# ATMEGA328P.net
KiCad netlist of a schematic drawn in EAGLE
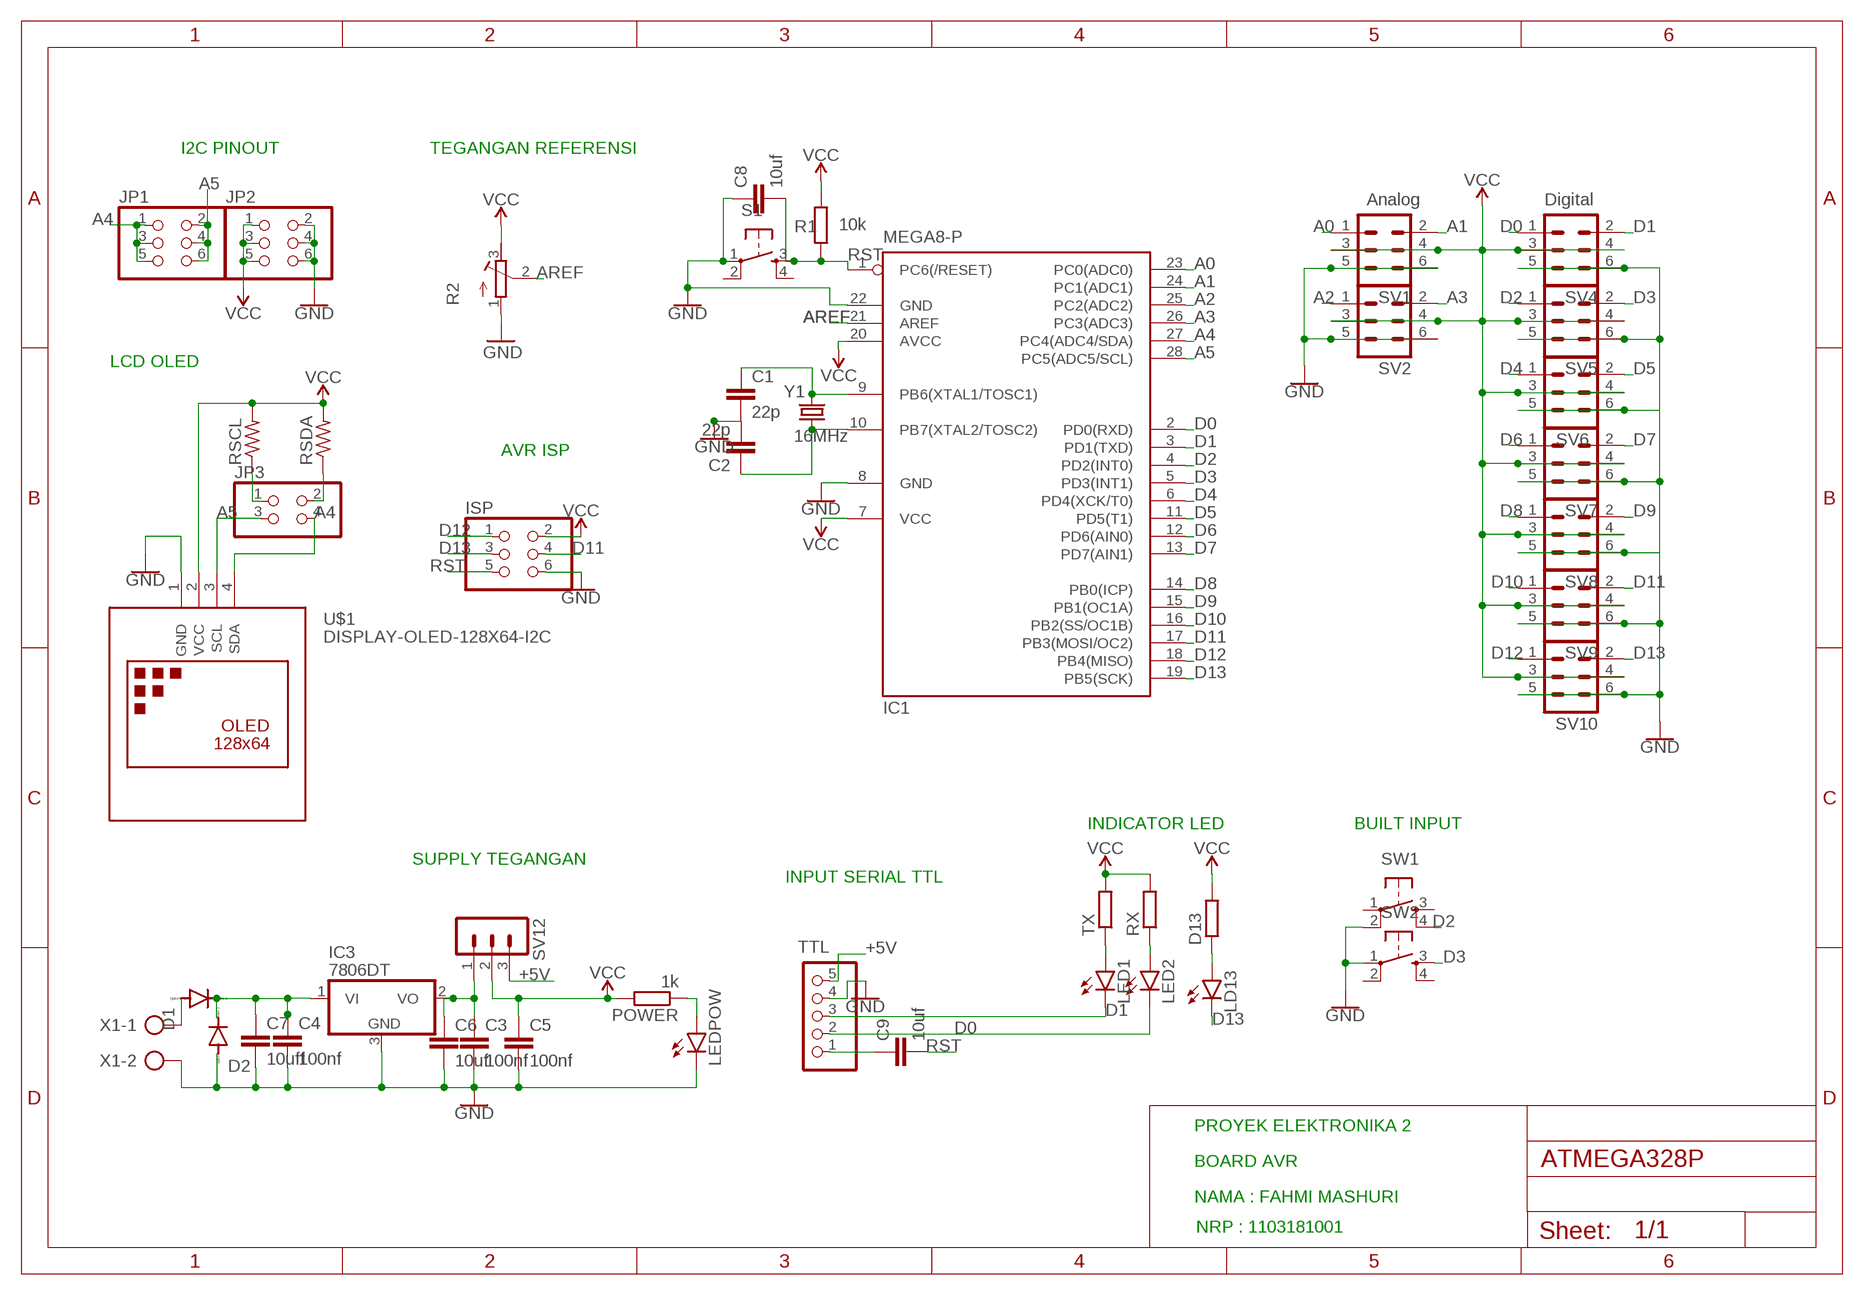
[diagram p0: schematic, sheet 1]

(export (version "E")
  (design (tool "Eeschema 10.0.6"))
  (components
    (comp (ref "C1")
      (value "22p")
      (footprint "eagle-import:C0805K")
      (libsource (lib "eagle-import") (part "C-EUC0805K"))
    )
    (comp (ref "C2")
      (value "22p")
      (footprint "eagle-import:C0805K")
      (libsource (lib "eagle-import") (part "C-EUC0805K"))
    )
    (comp (ref "C3")
      (value "100nf")
      (footprint "eagle-import:C0805K")
      (libsource (lib "eagle-import") (part "C-EUC0805K"))
    )
    (comp (ref "C4")
      (value "100nf")
      (footprint "eagle-import:C0805K")
      (libsource (lib "eagle-import") (part "C-EUC0805K"))
    )
    (comp (ref "C5")
      (value "100nf")
      (footprint "eagle-import:C0805K")
      (libsource (lib "eagle-import") (part "C-EUC0805K"))
    )
    (comp (ref "C6")
      (value "10uf")
      (footprint "eagle-import:C0805K")
      (libsource (lib "eagle-import") (part "C-EUC0805K"))
    )
    (comp (ref "C7")
      (value "10uff")
      (footprint "eagle-import:C0805K")
      (libsource (lib "eagle-import") (part "C-EUC0805K"))
    )
    (comp (ref "C8")
      (value "10uf")
      (footprint "eagle-import:C0805K")
      (libsource (lib "eagle-import") (part "C-EUC0805K"))
    )
    (comp (ref "C9")
      (value "10uf")
      (footprint "eagle-import:C0805K")
      (libsource (lib "eagle-import") (part "C-EUC0805K"))
    )
    (comp (ref "D1")
      (value "PURPLE")
      (footprint "eagle-import:SOD80C")
      (libsource (lib "eagle-import") (part "PMLL4150"))
    )
    (comp (ref "D2")
      (value "PURPLE")
      (footprint "eagle-import:SOD80C")
      (libsource (lib "eagle-import") (part "PMLL4150"))
    )
    (comp (ref "D13")
      (value "R-EU_R0805")
      (footprint "eagle-import:R0805")
      (libsource (lib "eagle-import") (part "R-EU_R0805"))
    )
    (comp (ref "IC1")
      (value "MEGA8-P")
      (footprint "eagle-import:DIL28-3")
      (libsource (lib "eagle-import") (part "MEGA8-P"))
    )
    (comp (ref "IC3")
      (value "7806DT")
      (footprint "eagle-import:TO252")
      (libsource (lib "eagle-import") (part "78DT06"))
    )
    (comp (ref "ISP")
      (value "PINHD-2X3")
      (footprint "eagle-import:2X03")
      (libsource (lib "eagle-import") (part "PINHD-2X3"))
    )
    (comp (ref "JP1")
      (value "PINHD-2X3")
      (footprint "eagle-import:2X03")
      (libsource (lib "eagle-import") (part "PINHD-2X3"))
    )
    (comp (ref "JP2")
      (value "PINHD-2X3")
      (footprint "eagle-import:2X03")
      (libsource (lib "eagle-import") (part "PINHD-2X3"))
    )
    (comp (ref "JP3")
      (value "PINHD-2X2")
      (footprint "eagle-import:2X02")
      (libsource (lib "eagle-import") (part "PINHD-2X2"))
    )
    (comp (ref "LD13")
      (value "LED3MM")
      (footprint "eagle-import:LED3MM")
      (libsource (lib "eagle-import") (part "LED3MM"))
    )
    (comp (ref "LED1")
      (value "LED3MM")
      (footprint "eagle-import:LED3MM")
      (libsource (lib "eagle-import") (part "LED3MM"))
    )
    (comp (ref "LED2")
      (value "LED3MM")
      (footprint "eagle-import:LED3MM")
      (libsource (lib "eagle-import") (part "LED3MM"))
    )
    (comp (ref "LEDPOW")
      (value "LED3MM")
      (footprint "eagle-import:LED3MM")
      (libsource (lib "eagle-import") (part "LED3MM"))
    )
    (comp (ref "POWER")
      (value "1k")
      (footprint "eagle-import:R0805")
      (libsource (lib "eagle-import") (part "R-EU_R0805"))
    )
    (comp (ref "R1")
      (value "10k")
      (footprint "eagle-import:R0805")
      (libsource (lib "eagle-import") (part "R-EU_R0805"))
    )
    (comp (ref "R2")
      (value "R-TRIMM64W")
      (footprint "eagle-import:RTRIM64W")
      (libsource (lib "eagle-import") (part "R-TRIMM64W"))
    )
    (comp (ref "RSCL")
      (value "R-US_R1206")
      (footprint "eagle-import:R1206")
      (libsource (lib "eagle-import") (part "R-US_R1206"))
    )
    (comp (ref "RSDA")
      (value "R-US_R1206")
      (footprint "eagle-import:R1206")
      (libsource (lib "eagle-import") (part "R-US_R1206"))
    )
    (comp (ref "RX")
      (value "R-EU_R0805")
      (footprint "eagle-import:R0805")
      (libsource (lib "eagle-import") (part "R-EU_R0805"))
    )
    (comp (ref "S1")
      (value "TAC_SWITCHPTH")
      (footprint "eagle-import:TACTILE-PTH")
      (libsource (lib "eagle-import") (part "TAC_SWITCHPTH"))
    )
    (comp (ref "SV1")
      (value "MA03-2")
      (footprint "eagle-import:MA03-2")
      (libsource (lib "eagle-import") (part "MA03-2"))
    )
    (comp (ref "SV2")
      (value "MA03-2")
      (footprint "eagle-import:MA03-2")
      (libsource (lib "eagle-import") (part "MA03-2"))
    )
    (comp (ref "SV4")
      (value "MA03-2")
      (footprint "eagle-import:MA03-2")
      (libsource (lib "eagle-import") (part "MA03-2"))
    )
    (comp (ref "SV5")
      (value "MA03-2")
      (footprint "eagle-import:MA03-2")
      (libsource (lib "eagle-import") (part "MA03-2"))
    )
    (comp (ref "SV6")
      (value "MA03-2")
      (footprint "eagle-import:MA03-2")
      (libsource (lib "eagle-import") (part "MA03-2"))
    )
    (comp (ref "SV7")
      (value "MA03-2")
      (footprint "eagle-import:MA03-2")
      (libsource (lib "eagle-import") (part "MA03-2"))
    )
    (comp (ref "SV8")
      (value "MA03-2")
      (footprint "eagle-import:MA03-2")
      (libsource (lib "eagle-import") (part "MA03-2"))
    )
    (comp (ref "SV9")
      (value "MA03-2")
      (footprint "eagle-import:MA03-2")
      (libsource (lib "eagle-import") (part "MA03-2"))
    )
    (comp (ref "SV10")
      (value "MA03-2")
      (footprint "eagle-import:MA03-2")
      (libsource (lib "eagle-import") (part "MA03-2"))
    )
    (comp (ref "SV12")
      (value "MA03-1")
      (footprint "eagle-import:MA03-1")
      (libsource (lib "eagle-import") (part "MA03-1"))
    )
    (comp (ref "SW1")
      (value "TAC_SWITCHPTH")
      (footprint "eagle-import:TACTILE-PTH")
      (libsource (lib "eagle-import") (part "TAC_SWITCHPTH"))
    )
    (comp (ref "SW2")
      (value "TAC_SWITCHPTH")
      (footprint "eagle-import:TACTILE-PTH")
      (libsource (lib "eagle-import") (part "TAC_SWITCHPTH"))
    )
    (comp (ref "TTL")
      (value "PINHD-1X5")
      (footprint "eagle-import:1X05")
      (libsource (lib "eagle-import") (part "PINHD-1X5"))
    )
    (comp (ref "TX")
      (value "R-EU_R0805")
      (footprint "eagle-import:R0805")
      (libsource (lib "eagle-import") (part "R-EU_R0805"))
    )
    (comp (ref "U$1")
      (value "DISPLAY-OLED-128X64-I2C")
      (footprint "eagle-import:DISPLAY-OLED-128X64-I2C")
      (libsource (lib "eagle-import") (part "DISPLAY-OLED-128X64-I2C"))
    )
    (comp (ref "X1")
      (value "AK500/2-H")
      (footprint "eagle-import:AK500_2-H")
      (libsource (lib "eagle-import") (part "AK500/2-H"))
    )
    (comp (ref "Y1")
      (value "16MHz")
      (footprint "eagle-import:HC49UP")
      (libsource (lib "eagle-import") (part "CRYSTALSMD-HC49UP"))
    )
  )
  (nets
    (net (code "1") (name "/+5V") (class "Default")
      (node (ref "SV12") (pin "3") (pinfunction "3_3") (pintype "passive"))
      (node (ref "TTL") (pin "5") (pinfunction "5_5") (pintype "passive"))
    )
    (net (code "2") (name "/A0") (class "Default")
      (node (ref "IC1") (pin "23") (pinfunction "PC0(ADC0)_23") (pintype "bidirectional"))
      (node (ref "SV1") (pin "1") (pinfunction "1_1") (pintype "passive"))
    )
    (net (code "3") (name "/A1") (class "Default")
      (node (ref "IC1") (pin "24") (pinfunction "PC1(ADC1)_24") (pintype "bidirectional"))
      (node (ref "SV1") (pin "2") (pinfunction "2_2") (pintype "passive"))
    )
    (net (code "4") (name "/A2") (class "Default")
      (node (ref "IC1") (pin "25") (pinfunction "PC2(ADC2)_25") (pintype "bidirectional"))
      (node (ref "SV2") (pin "1") (pinfunction "1_1") (pintype "passive"))
    )
    (net (code "5") (name "/A3") (class "Default")
      (node (ref "IC1") (pin "26") (pinfunction "PC3(ADC3)_26") (pintype "bidirectional"))
      (node (ref "SV2") (pin "2") (pinfunction "2_2") (pintype "passive"))
    )
    (net (code "6") (name "/A4") (class "Default")
      (node (ref "IC1") (pin "27") (pinfunction "PC4(ADC4/SDA)_27") (pintype "bidirectional"))
      (node (ref "JP1") (pin "1") (pinfunction "1_1") (pintype "passive"))
      (node (ref "JP1") (pin "3") (pinfunction "3_3") (pintype "passive"))
      (node (ref "JP1") (pin "5") (pinfunction "5_5") (pintype "passive"))
      (node (ref "JP3") (pin "4") (pinfunction "4_4") (pintype "passive"))
      (node (ref "U$1") (pin "4") (pinfunction "SDA_4") (pintype "bidirectional"))
    )
    (net (code "7") (name "/A5") (class "Default")
      (node (ref "IC1") (pin "28") (pinfunction "PC5(ADC5/SCL)_28") (pintype "bidirectional"))
      (node (ref "JP1") (pin "2") (pinfunction "2_2") (pintype "passive"))
      (node (ref "JP1") (pin "4") (pinfunction "4_4") (pintype "passive"))
      (node (ref "JP1") (pin "6") (pinfunction "6_6") (pintype "passive"))
      (node (ref "JP3") (pin "3") (pinfunction "3_3") (pintype "passive"))
      (node (ref "U$1") (pin "3") (pinfunction "SCL_3") (pintype "bidirectional"))
    )
    (net (code "8") (name "/AREF") (class "Default")
      (node (ref "IC1") (pin "21") (pinfunction "AREF_21") (pintype "passive"))
      (node (ref "R2") (pin "2") (pinfunction "S_2") (pintype "passive"))
    )
    (net (code "9") (name "/D0") (class "Default")
      (node (ref "IC1") (pin "2") (pinfunction "PD0(RXD)_2") (pintype "bidirectional"))
      (node (ref "LED2") (pin "K") (pinfunction "C_K") (pintype "passive"))
      (node (ref "SV4") (pin "1") (pinfunction "1_1") (pintype "passive"))
      (node (ref "TTL") (pin "2") (pinfunction "2_2") (pintype "passive"))
    )
    (net (code "10") (name "/D1") (class "Default")
      (node (ref "IC1") (pin "3") (pinfunction "PD1(TXD)_3") (pintype "bidirectional"))
      (node (ref "LED1") (pin "K") (pinfunction "C_K") (pintype "passive"))
      (node (ref "SV4") (pin "2") (pinfunction "2_2") (pintype "passive"))
      (node (ref "TTL") (pin "3") (pinfunction "3_3") (pintype "passive"))
    )
    (net (code "11") (name "/D2") (class "Default")
      (node (ref "IC1") (pin "4") (pinfunction "PD2(INT0)_4") (pintype "bidirectional"))
      (node (ref "SV5") (pin "1") (pinfunction "1_1") (pintype "passive"))
      (node (ref "SW1") (pin "4") (pinfunction "4_4") (pintype "passive"))
    )
    (net (code "12") (name "/D3") (class "Default")
      (node (ref "IC1") (pin "5") (pinfunction "PD3(INT1)_5") (pintype "bidirectional"))
      (node (ref "SV5") (pin "2") (pinfunction "2_2") (pintype "passive"))
      (node (ref "SW2") (pin "3") (pinfunction "3_3") (pintype "passive"))
    )
    (net (code "13") (name "/D4") (class "Default")
      (node (ref "IC1") (pin "6") (pinfunction "PD4(XCK/T0)_6") (pintype "bidirectional"))
      (node (ref "SV6") (pin "1") (pinfunction "1_1") (pintype "passive"))
    )
    (net (code "14") (name "/D5") (class "Default")
      (node (ref "IC1") (pin "11") (pinfunction "PD5(T1)_11") (pintype "bidirectional"))
      (node (ref "SV6") (pin "2") (pinfunction "2_2") (pintype "passive"))
    )
    (net (code "15") (name "/D6") (class "Default")
      (node (ref "IC1") (pin "12") (pinfunction "PD6(AIN0)_12") (pintype "bidirectional"))
      (node (ref "SV7") (pin "1") (pinfunction "1_1") (pintype "passive"))
    )
    (net (code "16") (name "/D7") (class "Default")
      (node (ref "IC1") (pin "13") (pinfunction "PD7(AIN1)_13") (pintype "bidirectional"))
      (node (ref "SV7") (pin "2") (pinfunction "2_2") (pintype "passive"))
    )
    (net (code "17") (name "/D8") (class "Default")
      (node (ref "IC1") (pin "14") (pinfunction "PB0(ICP)_14") (pintype "bidirectional"))
      (node (ref "SV8") (pin "1") (pinfunction "1_1") (pintype "passive"))
    )
    (net (code "18") (name "/D9") (class "Default")
      (node (ref "IC1") (pin "15") (pinfunction "PB1(OC1A)_15") (pintype "bidirectional"))
      (node (ref "SV8") (pin "2") (pinfunction "2_2") (pintype "passive"))
    )
    (net (code "19") (name "/D10") (class "Default")
      (node (ref "IC1") (pin "16") (pinfunction "PB2(SS/OC1B)_16") (pintype "bidirectional"))
      (node (ref "SV9") (pin "1") (pinfunction "1_1") (pintype "passive"))
    )
    (net (code "20") (name "/D11") (class "Default")
      (node (ref "IC1") (pin "17") (pinfunction "PB3(MOSI/OC2)_17") (pintype "bidirectional"))
      (node (ref "ISP") (pin "4") (pinfunction "4_4") (pintype "passive"))
      (node (ref "SV9") (pin "2") (pinfunction "2_2") (pintype "passive"))
    )
    (net (code "21") (name "/D12") (class "Default")
      (node (ref "IC1") (pin "18") (pinfunction "PB4(MISO)_18") (pintype "bidirectional"))
      (node (ref "ISP") (pin "1") (pinfunction "1_1") (pintype "passive"))
      (node (ref "SV10") (pin "1") (pinfunction "1_1") (pintype "passive"))
    )
    (net (code "22") (name "/D13") (class "Default")
      (node (ref "IC1") (pin "19") (pinfunction "PB5(SCK)_19") (pintype "bidirectional"))
      (node (ref "ISP") (pin "3") (pinfunction "3_3") (pintype "passive"))
      (node (ref "LD13") (pin "K") (pinfunction "C_K") (pintype "passive"))
      (node (ref "SV10") (pin "2") (pinfunction "2_2") (pintype "passive"))
    )
    (net (code "23") (name "/RST") (class "Default")
      (node (ref "C8") (pin "2") (pinfunction "2_2") (pintype "passive"))
      (node (ref "C9") (pin "2") (pinfunction "2_2") (pintype "passive"))
      (node (ref "IC1") (pin "1") (pinfunction "PC6(/RESET)_1") (pintype "bidirectional"))
      (node (ref "ISP") (pin "5") (pinfunction "5_5") (pintype "passive"))
      (node (ref "R1") (pin "1") (pinfunction "1_1") (pintype "passive"))
      (node (ref "S1") (pin "3") (pinfunction "3_3") (pintype "passive"))
    )
    (net (code "24") (name "GND") (class "Default")
      (node (ref "C1") (pin "2") (pinfunction "2_2") (pintype "passive"))
      (node (ref "C2") (pin "2") (pinfunction "2_2") (pintype "passive"))
      (node (ref "C3") (pin "2") (pinfunction "2_2") (pintype "passive"))
      (node (ref "C4") (pin "2") (pinfunction "2_2") (pintype "passive"))
      (node (ref "C5") (pin "2") (pinfunction "2_2") (pintype "passive"))
      (node (ref "C6") (pin "2") (pinfunction "2_2") (pintype "passive"))
      (node (ref "C7") (pin "2") (pinfunction "2_2") (pintype "passive"))
      (node (ref "C8") (pin "1") (pinfunction "1_1") (pintype "passive"))
      (node (ref "D2") (pin "A") (pinfunction "A_A") (pintype "passive"))
      (node (ref "IC1") (pin "22") (pinfunction "GND_22") (pintype "power_in"))
      (node (ref "IC1") (pin "8") (pinfunction "GND_8") (pintype "power_in"))
      (node (ref "IC3") (pin "3") (pinfunction "GND_3") (pintype "passive"))
      (node (ref "ISP") (pin "6") (pinfunction "6_6") (pintype "passive"))
      (node (ref "JP2") (pin "2") (pinfunction "2_2") (pintype "passive"))
      (node (ref "JP2") (pin "4") (pinfunction "4_4") (pintype "passive"))
      (node (ref "JP2") (pin "6") (pinfunction "6_6") (pintype "passive"))
      (node (ref "LEDPOW") (pin "K") (pinfunction "C_K") (pintype "passive"))
      (node (ref "R2") (pin "1") (pinfunction "A_1") (pintype "passive"))
      (node (ref "S1") (pin "1") (pinfunction "1_1") (pintype "passive"))
      (node (ref "SV1") (pin "5") (pinfunction "5_5") (pintype "passive"))
      (node (ref "SV1") (pin "6") (pinfunction "6_6") (pintype "passive"))
      (node (ref "SV10") (pin "5") (pinfunction "5_5") (pintype "passive"))
      (node (ref "SV10") (pin "6") (pinfunction "6_6") (pintype "passive"))
      (node (ref "SV2") (pin "5") (pinfunction "5_5") (pintype "passive"))
      (node (ref "SV2") (pin "6") (pinfunction "6_6") (pintype "passive"))
      (node (ref "SV4") (pin "5") (pinfunction "5_5") (pintype "passive"))
      (node (ref "SV4") (pin "6") (pinfunction "6_6") (pintype "passive"))
      (node (ref "SV5") (pin "5") (pinfunction "5_5") (pintype "passive"))
      (node (ref "SV5") (pin "6") (pinfunction "6_6") (pintype "passive"))
      (node (ref "SV6") (pin "5") (pinfunction "5_5") (pintype "passive"))
      (node (ref "SV6") (pin "6") (pinfunction "6_6") (pintype "passive"))
      (node (ref "SV7") (pin "5") (pinfunction "5_5") (pintype "passive"))
      (node (ref "SV7") (pin "6") (pinfunction "6_6") (pintype "passive"))
      (node (ref "SV8") (pin "5") (pinfunction "5_5") (pintype "passive"))
      (node (ref "SV8") (pin "6") (pinfunction "6_6") (pintype "passive"))
      (node (ref "SV9") (pin "5") (pinfunction "5_5") (pintype "passive"))
      (node (ref "SV9") (pin "6") (pinfunction "6_6") (pintype "passive"))
      (node (ref "SW1") (pin "2") (pinfunction "2_2") (pintype "passive"))
      (node (ref "SW2") (pin "1") (pinfunction "1_1") (pintype "passive"))
      (node (ref "TTL") (pin "4") (pinfunction "4_4") (pintype "passive"))
      (node (ref "U$1") (pin "1") (pinfunction "GND_1") (pintype "power_in"))
      (node (ref "X1") (pin "2") (pinfunction "KL_2") (pintype "passive"))
    )
    (net (code "25") (name "Net-(C9-Pad1)") (class "Default")
      (node (ref "C9") (pin "1") (pinfunction "1_1") (pintype "passive"))
      (node (ref "TTL") (pin "1") (pinfunction "1_1") (pintype "passive"))
    )
    (net (code "26") (name "Net-(D13-Pad1)") (class "Default")
      (node (ref "D13") (pin "1") (pinfunction "1_1") (pintype "passive"))
      (node (ref "LD13") (pin "A") (pinfunction "A_A") (pintype "passive"))
    )
    (net (code "27") (name "Net-(IC1-PB6(XTAL1{slash}TOSC1))") (class "Default")
      (node (ref "C1") (pin "1") (pinfunction "1_1") (pintype "passive"))
      (node (ref "IC1") (pin "9") (pinfunction "PB6(XTAL1/TOSC1)_9") (pintype "bidirectional"))
      (node (ref "Y1") (pin "2") (pinfunction "2_2") (pintype "passive"))
    )
    (net (code "28") (name "Net-(IC1-PB7(XTAL2{slash}TOSC2))") (class "Default")
      (node (ref "C2") (pin "1") (pinfunction "1_1") (pintype "passive"))
      (node (ref "IC1") (pin "10") (pinfunction "PB7(XTAL2/TOSC2)_10") (pintype "bidirectional"))
      (node (ref "Y1") (pin "1") (pinfunction "1_1") (pintype "passive"))
    )
    (net (code "29") (name "Net-(IC3-VI)") (class "Default")
      (node (ref "C4") (pin "1") (pinfunction "1_1") (pintype "passive"))
      (node (ref "C7") (pin "1") (pinfunction "1_1") (pintype "passive"))
      (node (ref "D1") (pin "C") (pinfunction "C_C") (pintype "passive"))
      (node (ref "D2") (pin "C") (pinfunction "C_C") (pintype "passive"))
      (node (ref "IC3") (pin "1") (pinfunction "VI_1") (pintype "input"))
    )
    (net (code "30") (name "Net-(IC3-VO)") (class "Default")
      (node (ref "C3") (pin "1") (pinfunction "1_1") (pintype "passive"))
      (node (ref "C6") (pin "1") (pinfunction "1_1") (pintype "passive"))
      (node (ref "IC3") (pin "2") (pinfunction "VO_2") (pintype "passive"))
      (node (ref "SV12") (pin "1") (pinfunction "1_1") (pintype "passive"))
    )
    (net (code "31") (name "Net-(JP3-Pad1)") (class "Default")
      (node (ref "JP3") (pin "1") (pinfunction "1_1") (pintype "passive"))
      (node (ref "RSCL") (pin "1") (pinfunction "1_1") (pintype "passive"))
    )
    (net (code "32") (name "Net-(JP3-Pad2)") (class "Default")
      (node (ref "JP3") (pin "2") (pinfunction "2_2") (pintype "passive"))
      (node (ref "RSDA") (pin "1") (pinfunction "1_1") (pintype "passive"))
    )
    (net (code "33") (name "Net-(LED1-PadA)") (class "Default")
      (node (ref "LED1") (pin "A") (pinfunction "A_A") (pintype "passive"))
      (node (ref "TX") (pin "1") (pinfunction "1_1") (pintype "passive"))
    )
    (net (code "34") (name "Net-(LED2-PadA)") (class "Default")
      (node (ref "LED2") (pin "A") (pinfunction "A_A") (pintype "passive"))
      (node (ref "RX") (pin "1") (pinfunction "1_1") (pintype "passive"))
    )
    (net (code "35") (name "Net-(LEDPOW-PadA)") (class "Default")
      (node (ref "LEDPOW") (pin "A") (pinfunction "A_A") (pintype "passive"))
      (node (ref "POWER") (pin "1") (pinfunction "1_1") (pintype "passive"))
    )
    (net (code "36") (name "Net-(X1A-KL)") (class "Default")
      (node (ref "D1") (pin "A") (pinfunction "A_A") (pintype "passive"))
      (node (ref "X1") (pin "1") (pinfunction "KL_1") (pintype "passive"))
    )
    (net (code "37") (name "VCC") (class "Default")
      (node (ref "C5") (pin "1") (pinfunction "1_1") (pintype "passive"))
      (node (ref "D13") (pin "2") (pinfunction "2_2") (pintype "passive"))
      (node (ref "IC1") (pin "20") (pinfunction "AVCC_20") (pintype "power_in"))
      (node (ref "IC1") (pin "7") (pinfunction "VCC_7") (pintype "power_in"))
      (node (ref "ISP") (pin "2") (pinfunction "2_2") (pintype "passive"))
      (node (ref "JP2") (pin "1") (pinfunction "1_1") (pintype "passive"))
      (node (ref "JP2") (pin "3") (pinfunction "3_3") (pintype "passive"))
      (node (ref "JP2") (pin "5") (pinfunction "5_5") (pintype "passive"))
      (node (ref "POWER") (pin "2") (pinfunction "2_2") (pintype "passive"))
      (node (ref "R1") (pin "2") (pinfunction "2_2") (pintype "passive"))
      (node (ref "R2") (pin "3") (pinfunction "E_3") (pintype "passive"))
      (node (ref "RSCL") (pin "2") (pinfunction "2_2") (pintype "passive"))
      (node (ref "RSDA") (pin "2") (pinfunction "2_2") (pintype "passive"))
      (node (ref "RX") (pin "2") (pinfunction "2_2") (pintype "passive"))
      (node (ref "SV1") (pin "3") (pinfunction "3_3") (pintype "passive"))
      (node (ref "SV1") (pin "4") (pinfunction "4_4") (pintype "passive"))
      (node (ref "SV10") (pin "3") (pinfunction "3_3") (pintype "passive"))
      (node (ref "SV10") (pin "4") (pinfunction "4_4") (pintype "passive"))
      (node (ref "SV12") (pin "2") (pinfunction "2_2") (pintype "passive"))
      (node (ref "SV2") (pin "3") (pinfunction "3_3") (pintype "passive"))
      (node (ref "SV2") (pin "4") (pinfunction "4_4") (pintype "passive"))
      (node (ref "SV4") (pin "3") (pinfunction "3_3") (pintype "passive"))
      (node (ref "SV4") (pin "4") (pinfunction "4_4") (pintype "passive"))
      (node (ref "SV5") (pin "3") (pinfunction "3_3") (pintype "passive"))
      (node (ref "SV5") (pin "4") (pinfunction "4_4") (pintype "passive"))
      (node (ref "SV6") (pin "3") (pinfunction "3_3") (pintype "passive"))
      (node (ref "SV6") (pin "4") (pinfunction "4_4") (pintype "passive"))
      (node (ref "SV7") (pin "3") (pinfunction "3_3") (pintype "passive"))
      (node (ref "SV7") (pin "4") (pinfunction "4_4") (pintype "passive"))
      (node (ref "SV8") (pin "3") (pinfunction "3_3") (pintype "passive"))
      (node (ref "SV8") (pin "4") (pinfunction "4_4") (pintype "passive"))
      (node (ref "SV9") (pin "3") (pinfunction "3_3") (pintype "passive"))
      (node (ref "SV9") (pin "4") (pinfunction "4_4") (pintype "passive"))
      (node (ref "TX") (pin "2") (pinfunction "2_2") (pintype "passive"))
      (node (ref "U$1") (pin "2") (pinfunction "VCC_2") (pintype "power_in"))
    )
    (net (code "38") (name "unconnected-(S1-Pad2)") (class "Default")
      (node (ref "S1") (pin "2") (pinfunction "2_2") (pintype "passive"))
    )
    (net (code "39") (name "unconnected-(S1-Pad4)") (class "Default")
      (node (ref "S1") (pin "4") (pinfunction "4_4") (pintype "passive"))
    )
    (net (code "40") (name "unconnected-(SW1-Pad1)") (class "Default")
      (node (ref "SW1") (pin "1") (pinfunction "1_1") (pintype "passive"))
    )
    (net (code "41") (name "unconnected-(SW1-Pad3)") (class "Default")
      (node (ref "SW1") (pin "3") (pinfunction "3_3") (pintype "passive"))
    )
    (net (code "42") (name "unconnected-(SW2-Pad2)") (class "Default")
      (node (ref "SW2") (pin "2") (pinfunction "2_2") (pintype "passive"))
    )
    (net (code "43") (name "unconnected-(SW2-Pad4)") (class "Default")
      (node (ref "SW2") (pin "4") (pinfunction "4_4") (pintype "passive"))
    )
  )
)
